# lampicka.net
KiCad netlist of a schematic drawn in EAGLE
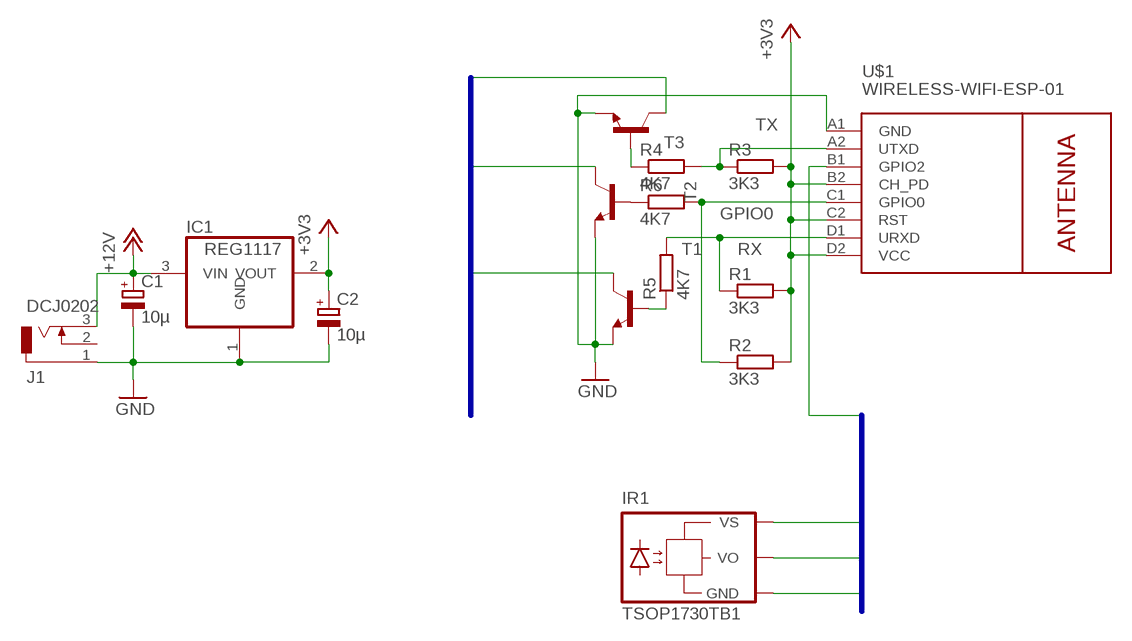
[diagram p0: schematic, sheet 1]

(export (version "E")
  (design (tool "Eeschema 10.0.6"))
  (components
    (comp (ref "C1")
      (value "10µ")
      (footprint "eagle-import:D_7343-31R")
      (libsource (lib "eagle-import") (part "CPOL-EUD/7343-31R"))
    )
    (comp (ref "C2")
      (value "10µ")
      (footprint "eagle-import:D_7343-31R")
      (libsource (lib "eagle-import") (part "CPOL-EUD/7343-31R"))
    )
    (comp (ref "IC1")
      (value "REG1117")
      (footprint "eagle-import:SOT223")
      (fields (field (name "SPICEPREFIX") "J"))
      (libsource (lib "eagle-import") (part "REG1117"))
    )
    (comp (ref "IR1")
      (value "TSOP1730TB1")
      (footprint "eagle-import:TSOP17_TB1")
      (libsource (lib "eagle-import") (part "TSOP17TB130"))
    )
    (comp (ref "J1")
      (value "DCJ0202")
      (footprint "eagle-import:DCJ0202")
      (libsource (lib "eagle-import") (part "DCJ0202"))
    )
    (comp (ref "R1")
      (value "3K3")
      (footprint "eagle-import:M1206")
      (libsource (lib "eagle-import") (part "R-EU_M1206"))
    )
    (comp (ref "R2")
      (value "3K3")
      (footprint "eagle-import:M1206")
      (libsource (lib "eagle-import") (part "R-EU_M1206"))
    )
    (comp (ref "R3")
      (value "3K3")
      (footprint "eagle-import:M1206")
      (libsource (lib "eagle-import") (part "R-EU_M1206"))
    )
    (comp (ref "R4")
      (value "4K7")
      (footprint "eagle-import:M1206")
      (libsource (lib "eagle-import") (part "R-EU_M1206"))
    )
    (comp (ref "R5")
      (value "4K7")
      (footprint "eagle-import:M1206")
      (libsource (lib "eagle-import") (part "R-EU_M1206"))
    )
    (comp (ref "R6")
      (value "4K7")
      (footprint "eagle-import:M1206")
      (libsource (lib "eagle-import") (part "R-EU_M1206"))
    )
    (comp (ref "T1")
      (value "MMBT2222ALT1-NPN-SOT23-BEC")
      (footprint "eagle-import:SOT23-BEC")
      (libsource (lib "eagle-import") (part "-NPN-SOT23-BECMMBT2222ALT1"))
    )
    (comp (ref "T2")
      (value "MMBT2222ALT1-NPN-SOT23-BEC")
      (footprint "eagle-import:SOT23-BEC")
      (libsource (lib "eagle-import") (part "-NPN-SOT23-BECMMBT2222ALT1"))
    )
    (comp (ref "T3")
      (value "MMBT2222ALT1-NPN-SOT23-BEC")
      (footprint "eagle-import:SOT23-BEC")
      (libsource (lib "eagle-import") (part "-NPN-SOT23-BECMMBT2222ALT1"))
    )
    (comp (ref "U$1")
      (value "WIRELESS-WIFI-ESP-01")
      (footprint "eagle-import:WIRELESS-WIFI-ESP-01")
      (libsource (lib "eagle-import") (part "WIRELESS-WIFI-ESP-01"))
    )
  )
  (nets
    (net (code "1") (name "+3V3") (class "Default")
      (node (ref "C2") (pin "+") (pinfunction "+_+") (pintype "passive"))
      (node (ref "IC1") (pin "2") (pinfunction "VOUT_2") (pintype "output"))
      (node (ref "IR1") (pin "VS") (pinfunction "VS_VS") (pintype "power_in"))
      (node (ref "R1") (pin "2") (pinfunction "2_2") (pintype "passive"))
      (node (ref "R2") (pin "2") (pinfunction "2_2") (pintype "passive"))
      (node (ref "R3") (pin "2") (pinfunction "2_2") (pintype "passive"))
      (node (ref "U$1") (pin "B2") (pinfunction "CH_PD_B2") (pintype "bidirectional"))
      (node (ref "U$1") (pin "C2") (pinfunction "RST_C2") (pintype "bidirectional"))
      (node (ref "U$1") (pin "D2") (pinfunction "VCC_D2") (pintype "power_in"))
    )
    (net (code "2") (name "+12V") (class "Default")
      (node (ref "C1") (pin "+") (pinfunction "+_+") (pintype "passive"))
      (node (ref "IC1") (pin "3") (pinfunction "VIN_3") (pintype "input"))
      (node (ref "J1") (pin "3") (pinfunction "3_3") (pintype "passive"))
    )
    (net (code "3") (name "/GPIO0") (class "Default")
      (node (ref "R2") (pin "1") (pinfunction "1_1") (pintype "passive"))
      (node (ref "R6") (pin "2") (pinfunction "2_2") (pintype "passive"))
      (node (ref "U$1") (pin "C1") (pinfunction "GPIO0_C1") (pintype "bidirectional"))
    )
    (net (code "4") (name "/IR") (class "Default")
      (node (ref "IR1") (pin "VO") (pinfunction "VO_VO") (pintype "open_collector"))
      (node (ref "U$1") (pin "B1") (pinfunction "GPIO2_B1") (pintype "bidirectional"))
    )
    (net (code "5") (name "/RX") (class "Default")
      (node (ref "R1") (pin "1") (pinfunction "1_1") (pintype "passive"))
      (node (ref "R5") (pin "2") (pinfunction "2_2") (pintype "passive"))
      (node (ref "U$1") (pin "D1") (pinfunction "URXD_D1") (pintype "bidirectional"))
    )
    (net (code "6") (name "/TX") (class "Default")
      (node (ref "R3") (pin "1") (pinfunction "1_1") (pintype "passive"))
      (node (ref "R4") (pin "2") (pinfunction "2_2") (pintype "passive"))
      (node (ref "U$1") (pin "A2") (pinfunction "UTXD_A2") (pintype "bidirectional"))
    )
    (net (code "7") (name "GND") (class "Default")
      (node (ref "C1") (pin "-") (pinfunction "-_-") (pintype "passive"))
      (node (ref "C2") (pin "-") (pinfunction "-_-") (pintype "passive"))
      (node (ref "IC1") (pin "1") (pinfunction "GND_1") (pintype "power_in"))
      (node (ref "IR1") (pin "GND") (pinfunction "GND_GND") (pintype "power_in"))
      (node (ref "J1") (pin "1") (pinfunction "1_1") (pintype "passive"))
      (node (ref "T1") (pin "E") (pinfunction "E_E") (pintype "passive"))
      (node (ref "T2") (pin "E") (pinfunction "E_E") (pintype "passive"))
      (node (ref "T3") (pin "E") (pinfunction "E_E") (pintype "passive"))
      (node (ref "U$1") (pin "A1") (pinfunction "GND_A1") (pintype "power_in"))
    )
    (net (code "8") (name "Net-(R4-Pad1)") (class "Default")
      (node (ref "R4") (pin "1") (pinfunction "1_1") (pintype "passive"))
      (node (ref "T2") (pin "B") (pinfunction "B_B") (pintype "passive"))
    )
    (net (code "9") (name "Net-(R5-Pad1)") (class "Default")
      (node (ref "R5") (pin "1") (pinfunction "1_1") (pintype "passive"))
      (node (ref "T1") (pin "B") (pinfunction "B_B") (pintype "passive"))
    )
    (net (code "10") (name "Net-(R6-Pad1)") (class "Default")
      (node (ref "R6") (pin "1") (pinfunction "1_1") (pintype "passive"))
      (node (ref "T3") (pin "B") (pinfunction "B_B") (pintype "passive"))
    )
    (net (code "11") (name "unconnected-(J1-Pad2)") (class "Default")
      (node (ref "J1") (pin "2") (pinfunction "2_2") (pintype "passive"))
    )
    (net (code "12") (name "unconnected-(T1-PadC)") (class "Default")
      (node (ref "T1") (pin "C") (pinfunction "C_C") (pintype "passive"))
    )
    (net (code "13") (name "unconnected-(T2-PadC)") (class "Default")
      (node (ref "T2") (pin "C") (pinfunction "C_C") (pintype "passive"))
    )
    (net (code "14") (name "unconnected-(T3-PadC)") (class "Default")
      (node (ref "T3") (pin "C") (pinfunction "C_C") (pintype "passive"))
    )
  )
)
